# 5_-OPI_MAIN.net
KiCad netlist of a schematic drawn in Altium Designer
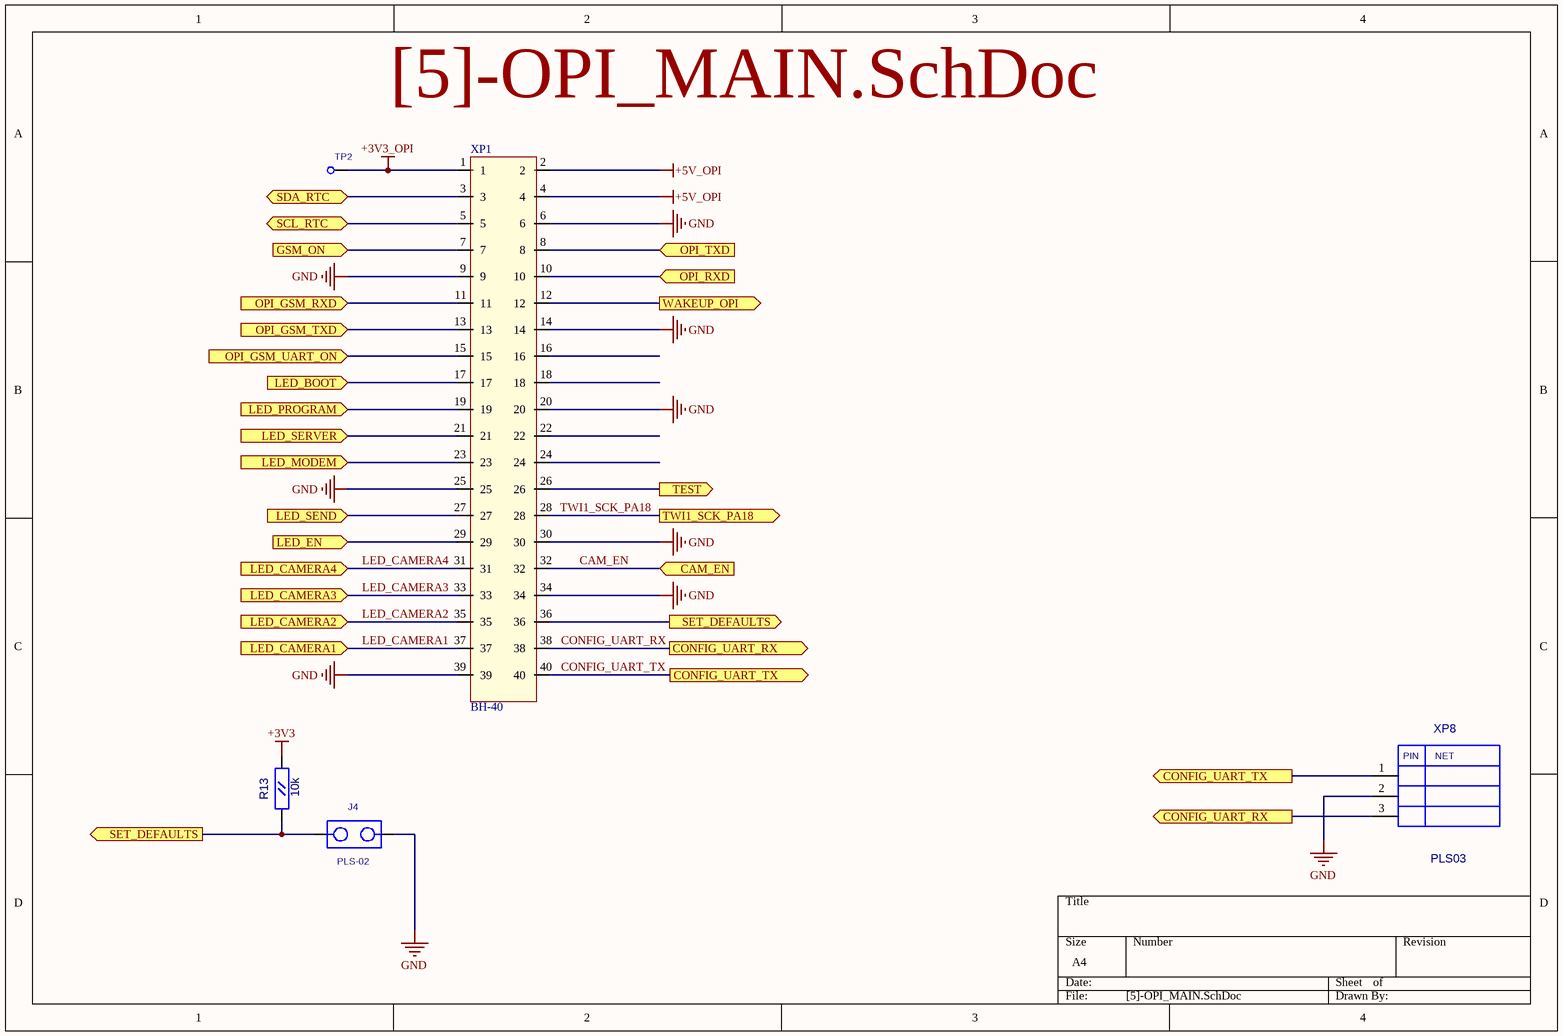
[diagram p0: [5]-OPI_MAIN.SchDoc]

(export (version "E")
  (design (tool "Eeschema 10.0.6"))
  (components
    (comp (ref "J4") (value "PLS-02") (footprint "PLS-02") (libsource (lib "fizik_lib") (part "PLS-02")))
    (comp (ref "R13")
      (value "10k")
      (footprint "RC0603")
      (description "RC0603")
      (libsource (lib "fizik_lib") (part "RC0603"))
    )
    (comp (ref "TP2")
      (value "TESTPOINT1")
      (footprint "TESTPOINT1")
      (libsource (lib "fizik_lib") (part "TESTPOINT1"))
    )
    (comp (ref "XP1")
      (value "BH-40")
      (footprint "BH-40")
      (description "2.54mm connector with key")
      (libsource (lib "fizik_lib") (part "BH-40"))
    )
    (comp (ref "XP8") (value "PLS03") (footprint "PLS-03") (libsource (lib "fizik_lib") (part "PLS03")))
  )
  (nets
    (net (code "1") (name "+3V3") (class "Default")
      (node (ref "R13") (pin "2") (pinfunction "B_2") (pintype "passive"))
    )
    (net (code "2") (name "+3V3_OPI") (class "Default")
      (node (ref "TP2") (pin "1") (pintype "passive"))
      (node (ref "XP1") (pin "1") (pinfunction "1_1") (pintype "passive"))
    )
    (net (code "3") (name "+5V_OPI") (class "Default")
      (node (ref "XP1") (pin "2") (pinfunction "2_2") (pintype "passive"))
      (node (ref "XP1") (pin "4") (pinfunction "4_4") (pintype "passive"))
    )
    (net (code "4") (name "/CAM_EN") (class "Default")
      (node (ref "XP1") (pin "32") (pinfunction "32_32") (pintype "passive"))
    )
    (net (code "5") (name "/CONFIG_UART_RX") (class "Default")
      (node (ref "XP1") (pin "38") (pinfunction "38_38") (pintype "passive"))
      (node (ref "XP8") (pin "3") (pinfunction "3_3") (pintype "passive"))
    )
    (net (code "6") (name "/CONFIG_UART_TX") (class "Default")
      (node (ref "XP1") (pin "40") (pinfunction "40_40") (pintype "passive"))
      (node (ref "XP8") (pin "1") (pinfunction "1_1") (pintype "passive"))
    )
    (net (code "7") (name "/GSM_ON") (class "Default")
      (node (ref "XP1") (pin "7") (pinfunction "7_7") (pintype "passive"))
    )
    (net (code "8") (name "/LED_BOOT") (class "Default")
      (node (ref "XP1") (pin "17") (pinfunction "17_17") (pintype "passive"))
    )
    (net (code "9") (name "/LED_CAMERA1") (class "Default")
      (node (ref "XP1") (pin "37") (pinfunction "37_37") (pintype "passive"))
    )
    (net (code "10") (name "/LED_CAMERA2") (class "Default")
      (node (ref "XP1") (pin "35") (pinfunction "35_35") (pintype "passive"))
    )
    (net (code "11") (name "/LED_CAMERA3") (class "Default")
      (node (ref "XP1") (pin "33") (pinfunction "33_33") (pintype "passive"))
    )
    (net (code "12") (name "/LED_CAMERA4") (class "Default")
      (node (ref "XP1") (pin "31") (pinfunction "31_31") (pintype "passive"))
    )
    (net (code "13") (name "/LED_EN") (class "Default")
      (node (ref "XP1") (pin "29") (pinfunction "29_29") (pintype "passive"))
    )
    (net (code "14") (name "/LED_MODEM") (class "Default")
      (node (ref "XP1") (pin "23") (pinfunction "23_23") (pintype "passive"))
    )
    (net (code "15") (name "/LED_PROGRAM") (class "Default")
      (node (ref "XP1") (pin "19") (pinfunction "19_19") (pintype "passive"))
    )
    (net (code "16") (name "/LED_SEND") (class "Default")
      (node (ref "XP1") (pin "27") (pinfunction "27_27") (pintype "passive"))
    )
    (net (code "17") (name "/LED_SERVER") (class "Default")
      (node (ref "XP1") (pin "21") (pinfunction "21_21") (pintype "passive"))
    )
    (net (code "18") (name "/OPI_GSM_RXD") (class "Default")
      (node (ref "XP1") (pin "11") (pinfunction "11_11") (pintype "passive"))
    )
    (net (code "19") (name "/OPI_GSM_TXD") (class "Default")
      (node (ref "XP1") (pin "13") (pinfunction "13_13") (pintype "passive"))
    )
    (net (code "20") (name "/OPI_GSM_UART_ON") (class "Default")
      (node (ref "XP1") (pin "15") (pinfunction "15_15") (pintype "passive"))
    )
    (net (code "21") (name "/OPI_RXD") (class "Default")
      (node (ref "XP1") (pin "10") (pinfunction "10_10") (pintype "passive"))
    )
    (net (code "22") (name "/OPI_TXD") (class "Default")
      (node (ref "XP1") (pin "8") (pinfunction "8_8") (pintype "passive"))
    )
    (net (code "23") (name "/SCL_RTC") (class "Default")
      (node (ref "XP1") (pin "5") (pinfunction "5_5") (pintype "passive"))
    )
    (net (code "24") (name "/SDA_RTC") (class "Default")
      (node (ref "XP1") (pin "3") (pinfunction "3_3") (pintype "passive"))
    )
    (net (code "25") (name "/SET_DEFAULTS") (class "Default")
      (node (ref "J4") (pin "1") (pintype "passive"))
      (node (ref "R13") (pin "1") (pinfunction "A_1") (pintype "passive"))
      (node (ref "XP1") (pin "36") (pinfunction "36_36") (pintype "passive"))
    )
    (net (code "26") (name "/TEST") (class "Default")
      (node (ref "XP1") (pin "26") (pinfunction "26_26") (pintype "passive"))
    )
    (net (code "27") (name "/TWI1_SCK_PA18") (class "Default")
      (node (ref "XP1") (pin "28") (pinfunction "28_28") (pintype "passive"))
    )
    (net (code "28") (name "/WAKEUP_OPI") (class "Default")
      (node (ref "XP1") (pin "12") (pinfunction "12_12") (pintype "passive"))
    )
    (net (code "29") (name "GND") (class "Default")
      (node (ref "J4") (pin "2") (pintype "passive"))
      (node (ref "XP1") (pin "14") (pinfunction "14_14") (pintype "passive"))
      (node (ref "XP1") (pin "20") (pinfunction "20_20") (pintype "passive"))
      (node (ref "XP1") (pin "25") (pinfunction "25_25") (pintype "passive"))
      (node (ref "XP1") (pin "30") (pinfunction "30_30") (pintype "passive"))
      (node (ref "XP1") (pin "34") (pinfunction "34_34") (pintype "passive"))
      (node (ref "XP1") (pin "39") (pinfunction "39_39") (pintype "passive"))
      (node (ref "XP1") (pin "6") (pinfunction "6_6") (pintype "passive"))
      (node (ref "XP1") (pin "9") (pinfunction "9_9") (pintype "passive"))
      (node (ref "XP8") (pin "2") (pinfunction "2_2") (pintype "passive"))
    )
    (net (code "30") (name "unconnected-(XP1-Pad16)") (class "Default")
      (node (ref "XP1") (pin "16") (pinfunction "16_16") (pintype "passive"))
    )
    (net (code "31") (name "unconnected-(XP1-Pad18)") (class "Default")
      (node (ref "XP1") (pin "18") (pinfunction "18_18") (pintype "passive"))
    )
    (net (code "32") (name "unconnected-(XP1-Pad22)") (class "Default")
      (node (ref "XP1") (pin "22") (pinfunction "22_22") (pintype "passive"))
    )
    (net (code "33") (name "unconnected-(XP1-Pad24)") (class "Default")
      (node (ref "XP1") (pin "24") (pinfunction "24_24") (pintype "passive"))
    )
  )
)
